# thevenin_equivalent.net
KiCad netlist of a schematic drawn in EasyEDA
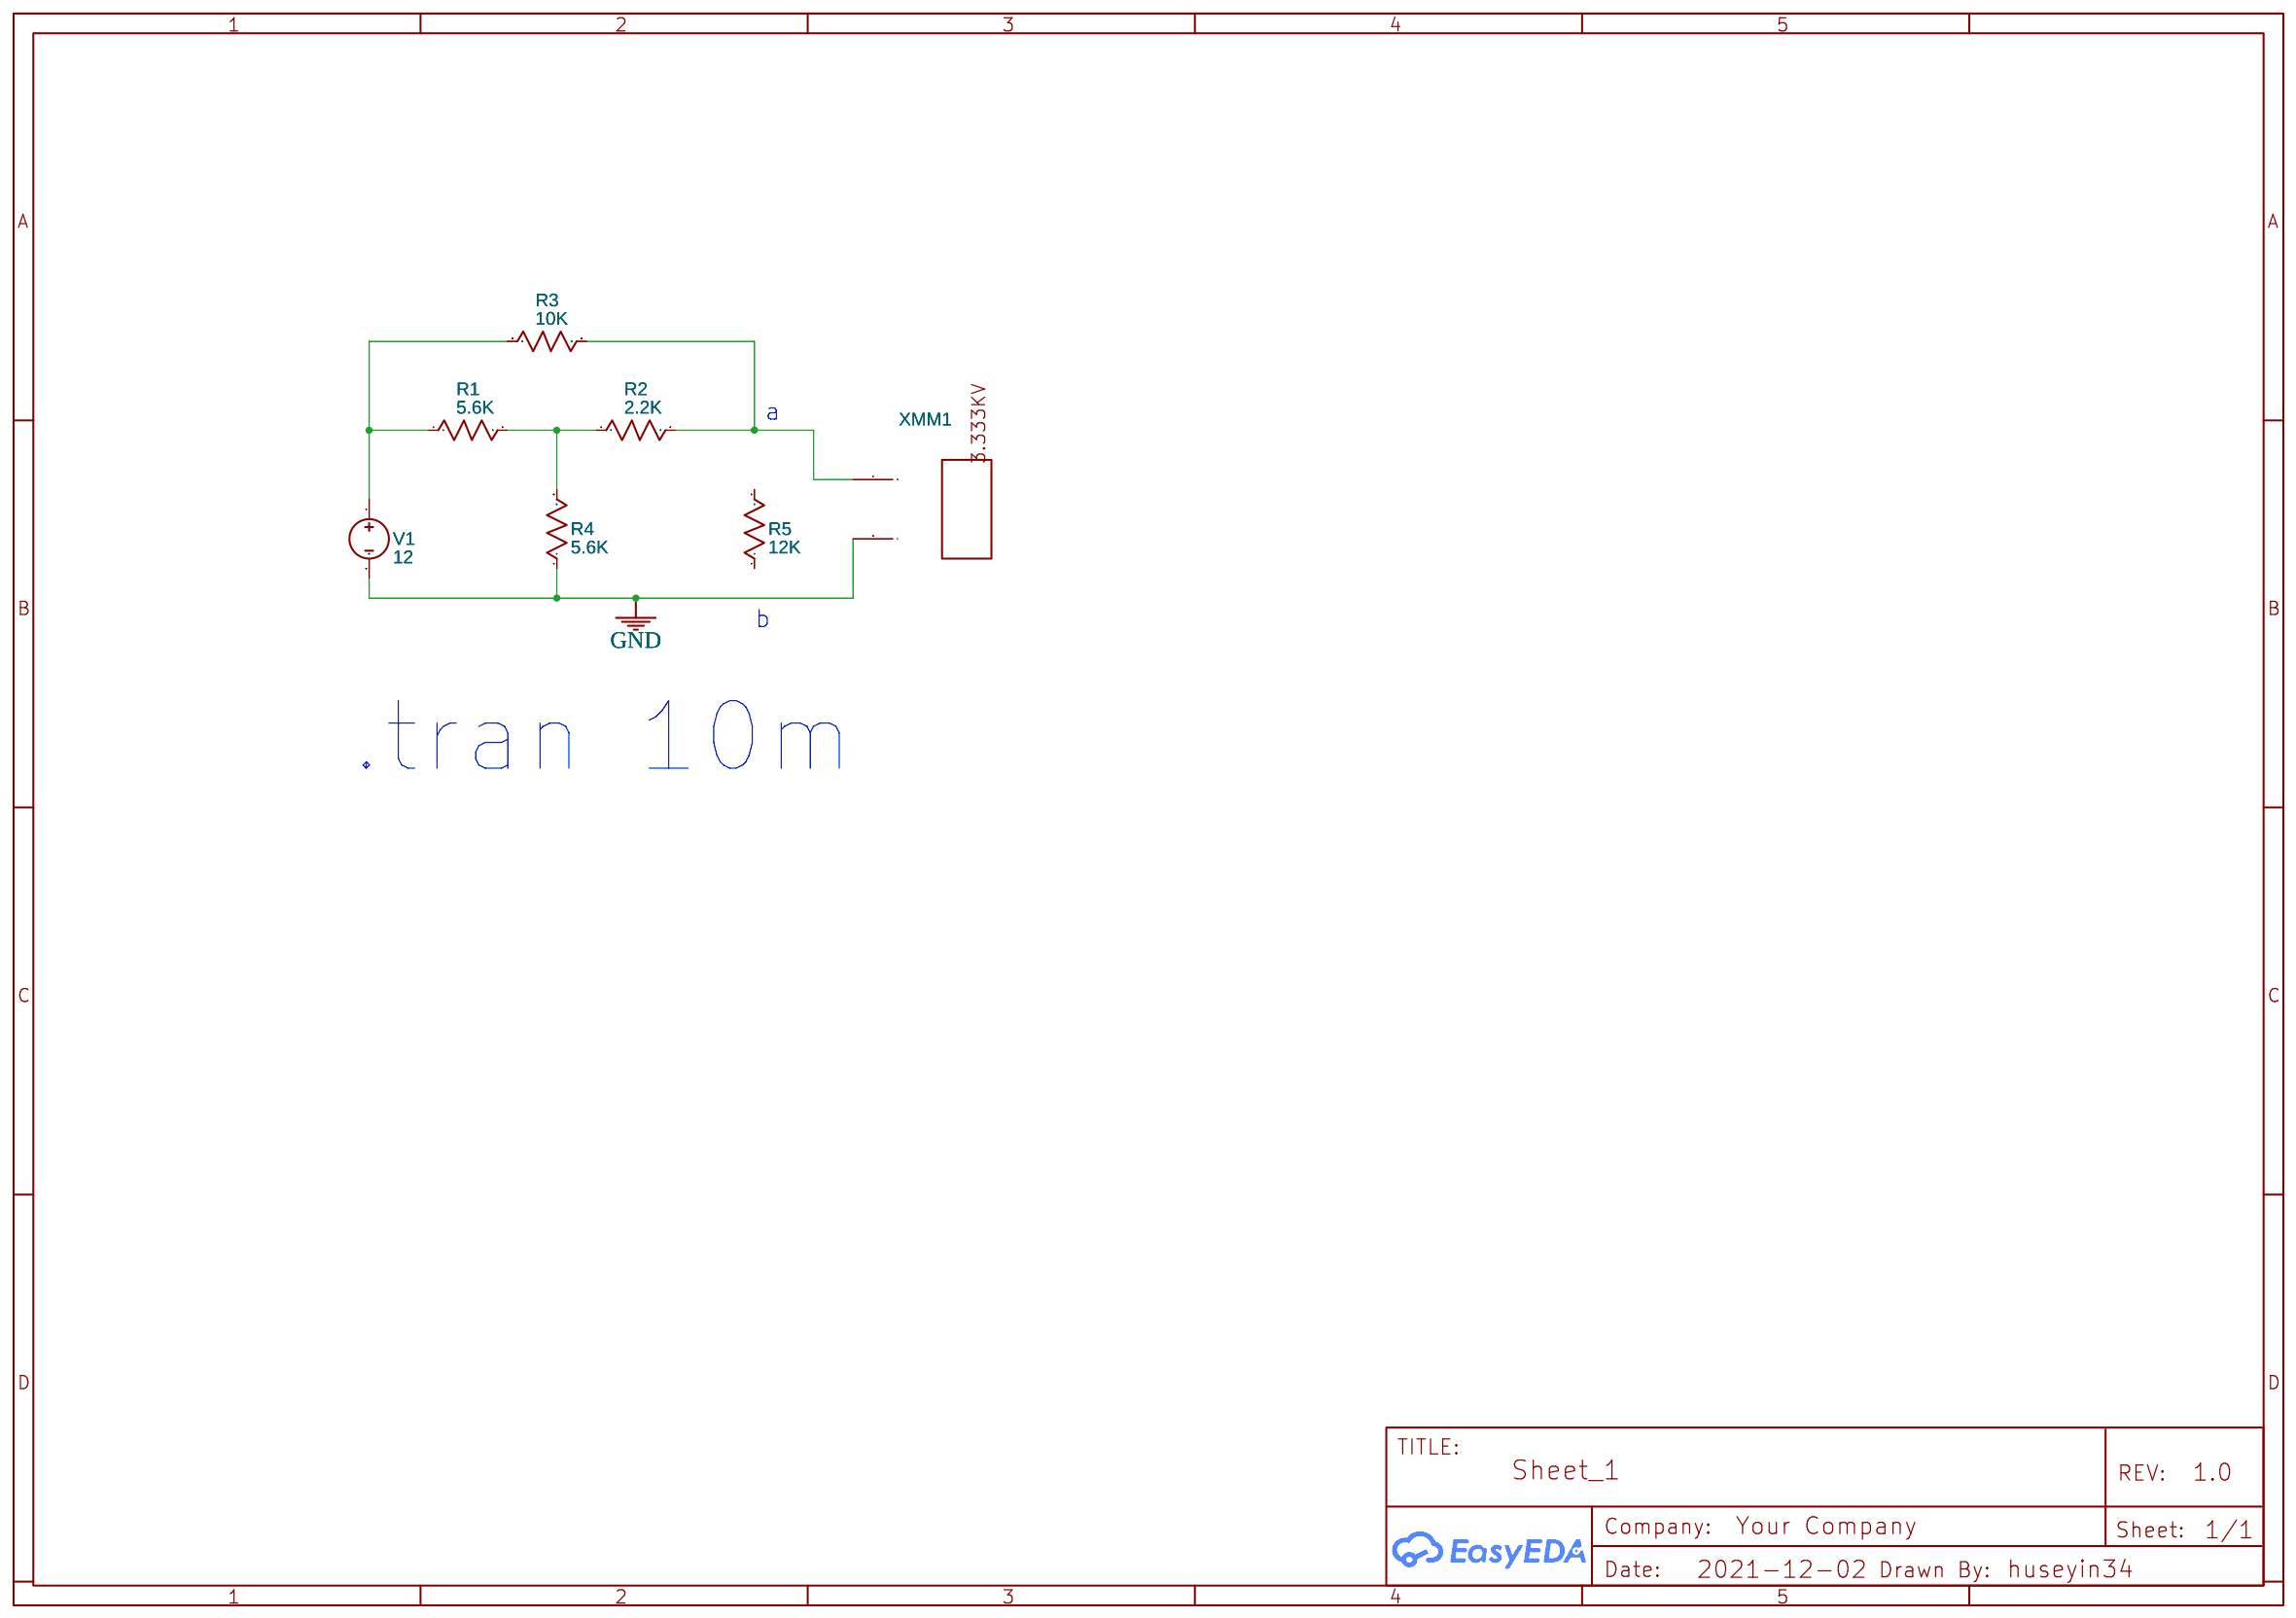
[diagram p0: fig3]
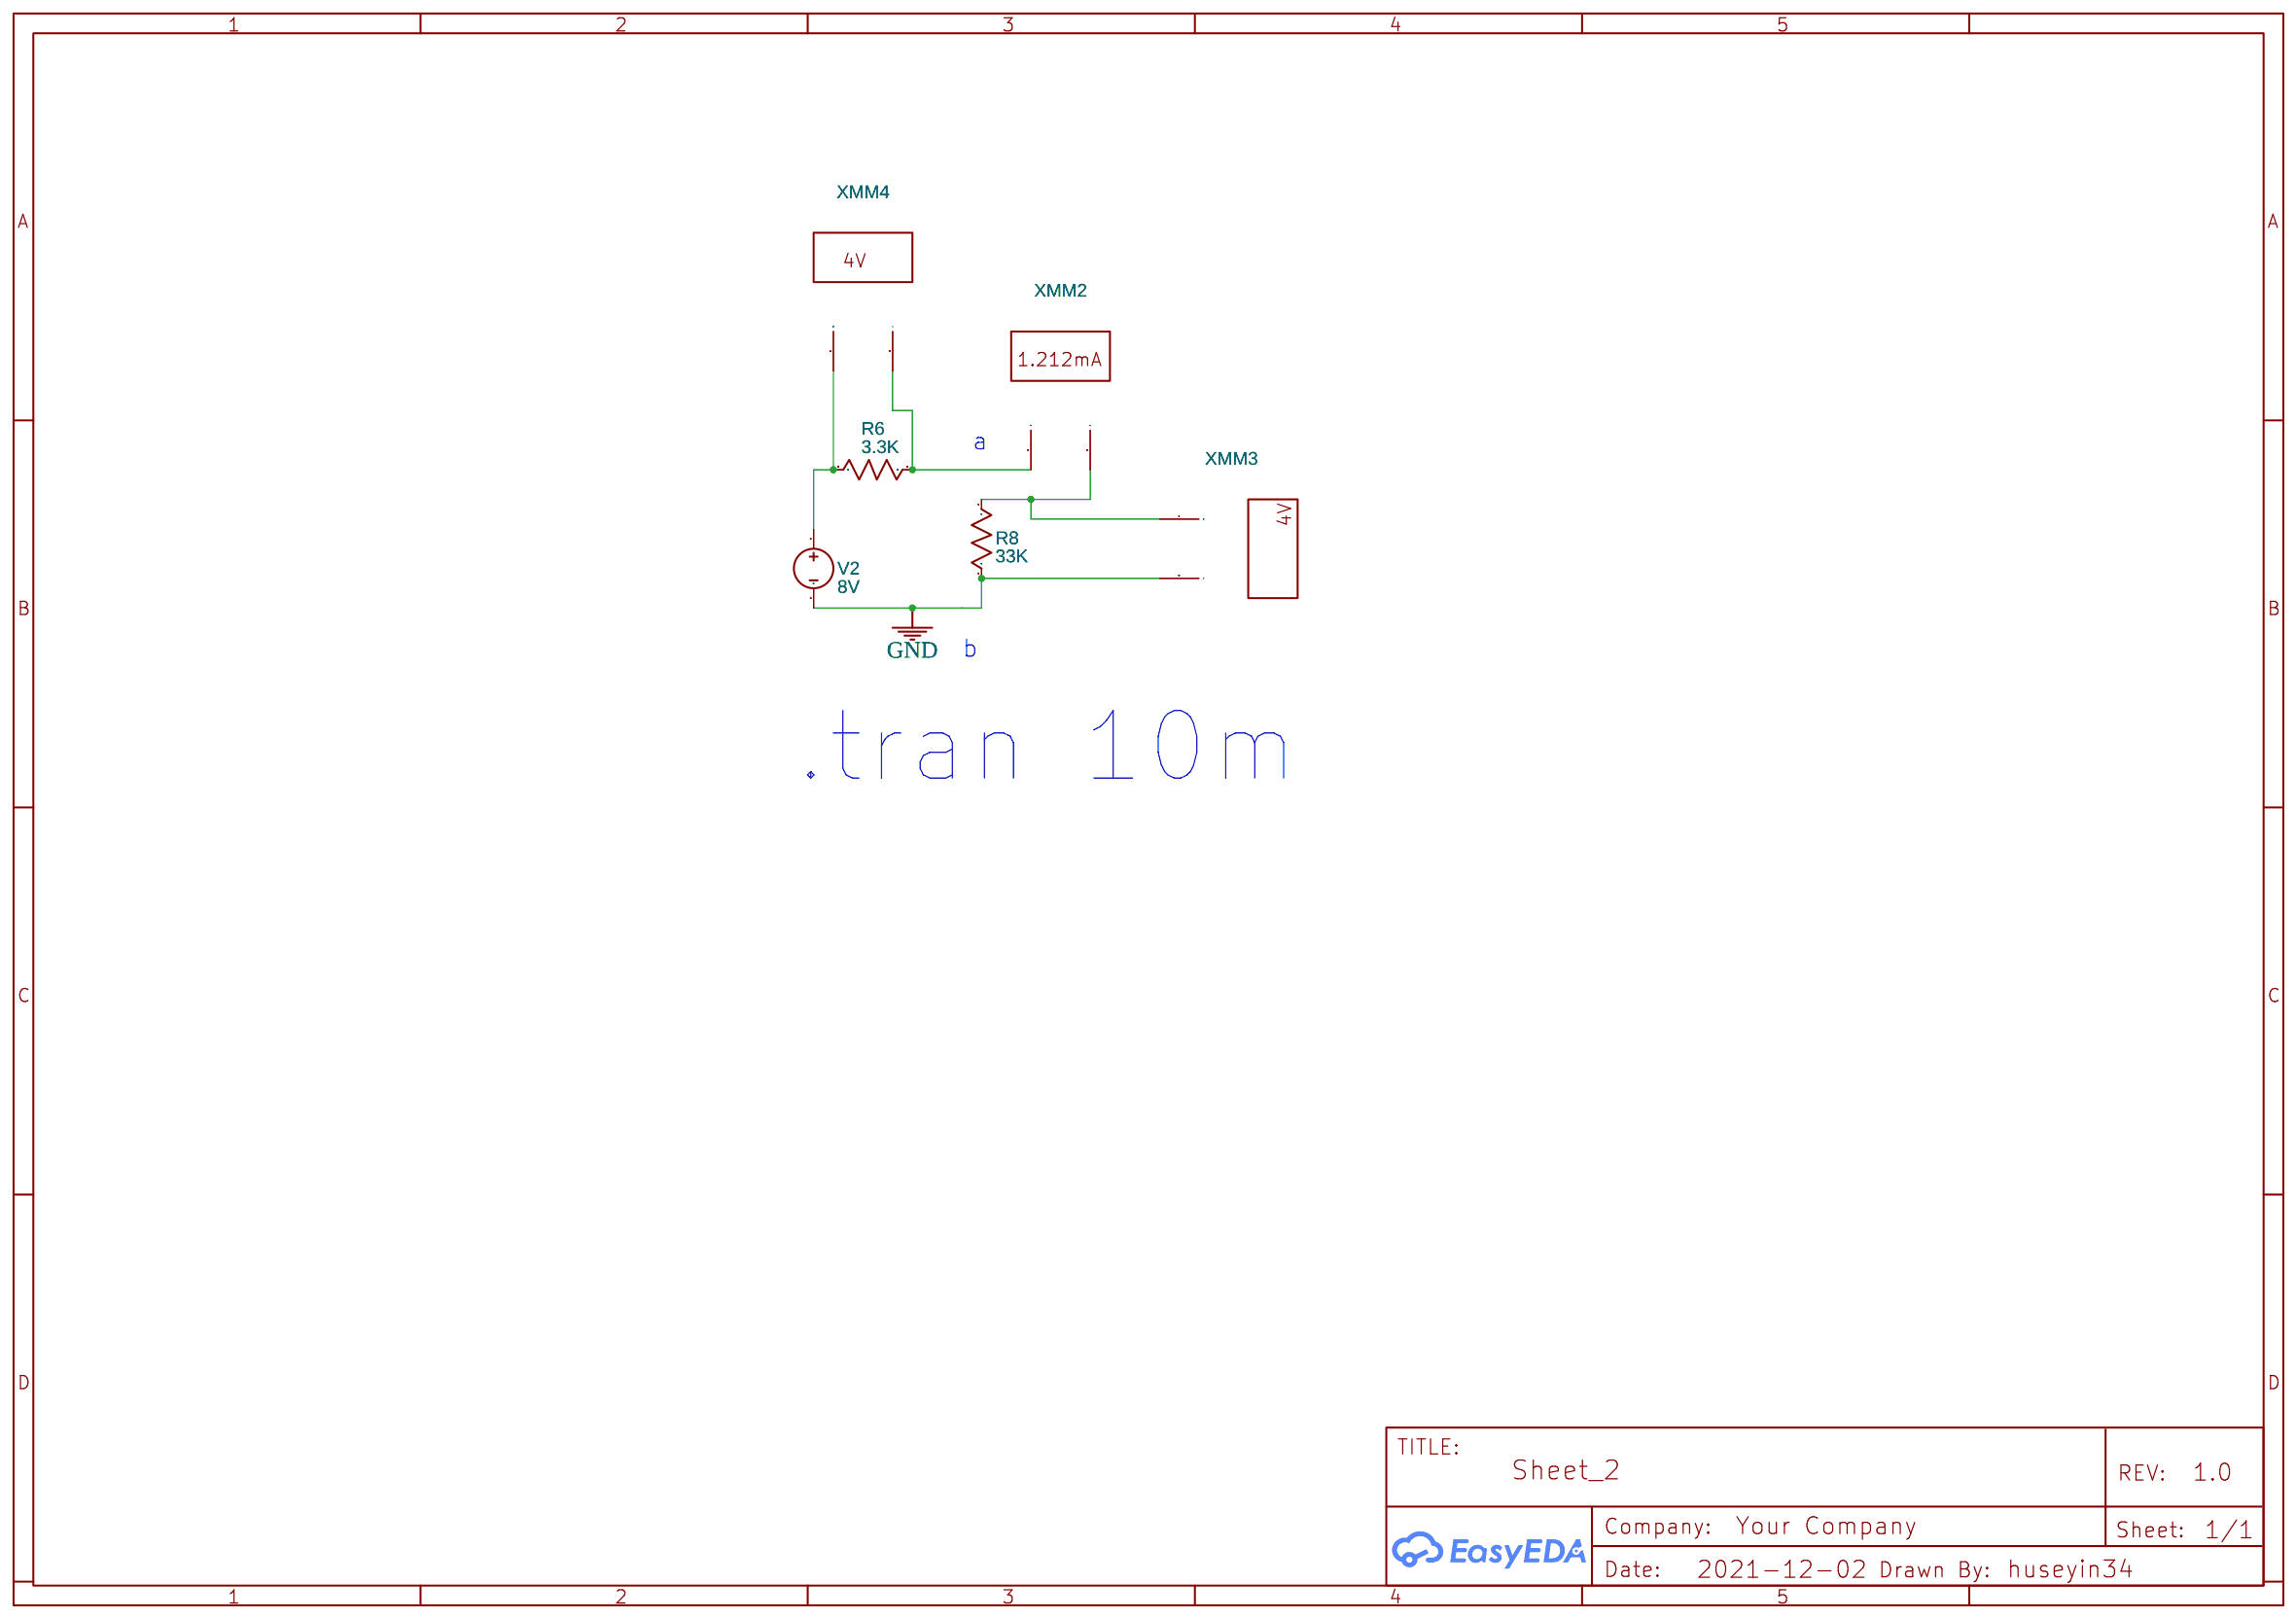
[diagram p1: thevenin equiv]
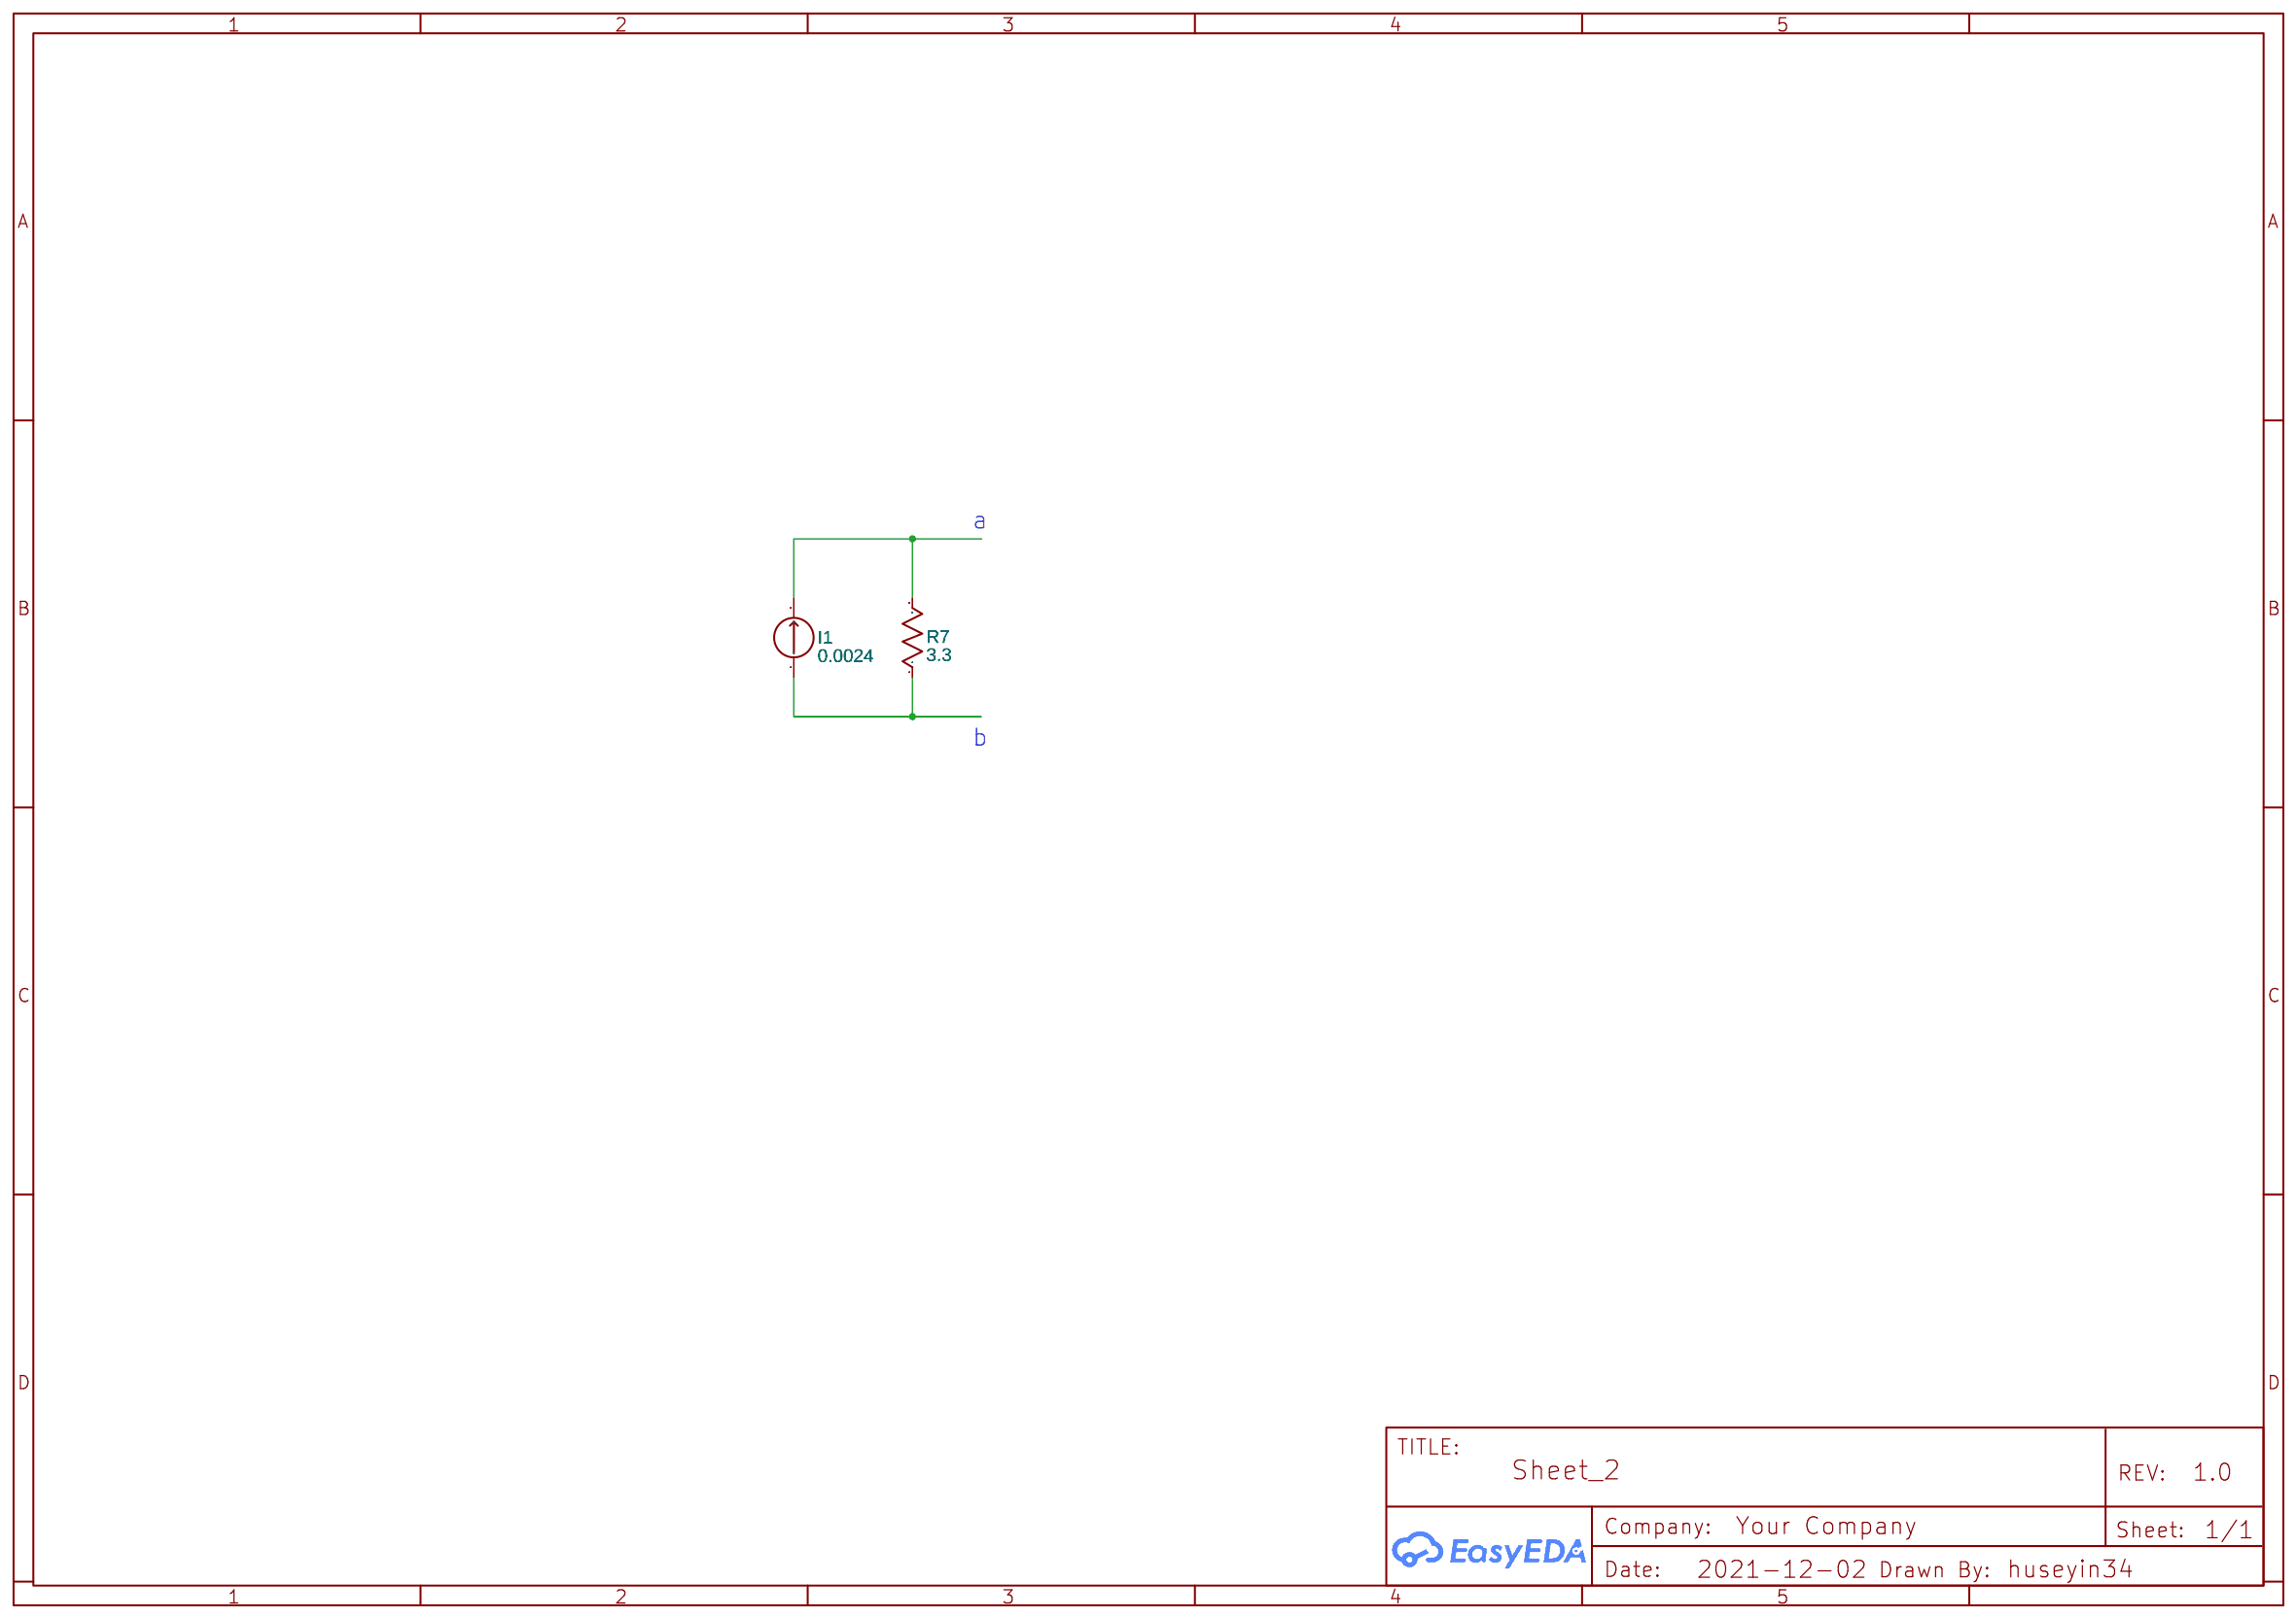
[diagram p2: Norton Equiv.]

(export (version "E")
  (design (tool "Eeschema 10.0.6"))
  (components
    (comp (ref "R1") (value "5.6K") (libsource (lib "") (part "Resistor_US_1")))
    (comp (ref "R2") (value "2.2K") (libsource (lib "") (part "Resistor_US_1")))
    (comp (ref "R3") (value "10K") (libsource (lib "") (part "Resistor_US_1")))
    (comp (ref "R4") (value "5.6K") (libsource (lib "") (part "Resistor_US")))
    (comp (ref "R5") (value "12K") (libsource (lib "") (part "Resistor_US")))
    (comp (ref "V1") (value "12") (libsource (lib "") (part "VDC")))
    (comp (ref "XMM1") (value "Multimeter") (libsource (lib "") (part "MULTIMETER")))
    (comp (ref "R6") (value "3.3K") (libsource (lib "") (part "Resistor_US")))
    (comp (ref "R8") (value "33K") (libsource (lib "") (part "Resistor_US_1")))
    (comp (ref "V2") (value "8V") (libsource (lib "") (part "VDC")))
    (comp (ref "XMM2") (value "Multimeter") (libsource (lib "") (part "MULTIMETER_2")))
    (comp (ref "XMM3") (value "Multimeter") (libsource (lib "") (part "MULTIMETER")))
    (comp (ref "XMM4") (value "Multimeter") (libsource (lib "") (part "MULTIMETER_1")))
    (comp (ref "I1") (value "0.0024") (libsource (lib "") (part "IDC")))
    (comp (ref "R7") (value "3.3") (libsource (lib "") (part "Resistor_US")))
  )
  (nets
    (net (code "1") (name "GND") (class "Default")
      (node (ref "R4") (pin "1") (pinfunction "1_1") (pintype "unspecified"))
      (node (ref "R8") (pin "1") (pinfunction "1_1") (pintype "unspecified"))
      (node (ref "V1") (pin "2") (pinfunction "2_2") (pintype "unspecified"))
      (node (ref "V2") (pin "2") (pinfunction "2_2") (pintype "unspecified"))
      (node (ref "XMM1") (pin "2") (pinfunction "I_2") (pintype "unspecified"))
      (node (ref "XMM3") (pin "2") (pinfunction "I_2") (pintype "unspecified"))
    )
    (net (code "2") (name "Net-(I1-Pad1)") (class "Default")
      (node (ref "I1") (pin "1") (pinfunction "1_1") (pintype "unspecified"))
      (node (ref "R7") (pin "1") (pinfunction "1_1") (pintype "unspecified"))
    )
    (net (code "3") (name "Net-(I1-Pad2)") (class "Default")
      (node (ref "I1") (pin "2") (pinfunction "2_2") (pintype "unspecified"))
      (node (ref "R7") (pin "2") (pinfunction "2_2") (pintype "unspecified"))
    )
    (net (code "4") (name "Net-(R1-Pad1)") (class "Default")
      (node (ref "R1") (pin "1") (pinfunction "1_1") (pintype "unspecified"))
      (node (ref "R3") (pin "1") (pinfunction "1_1") (pintype "unspecified"))
      (node (ref "V1") (pin "1") (pinfunction "1_1") (pintype "unspecified"))
    )
    (net (code "5") (name "Net-(R1-Pad2)") (class "Default")
      (node (ref "R1") (pin "2") (pinfunction "2_2") (pintype "unspecified"))
      (node (ref "R2") (pin "1") (pinfunction "1_1") (pintype "unspecified"))
      (node (ref "R4") (pin "2") (pinfunction "2_2") (pintype "unspecified"))
    )
    (net (code "6") (name "Net-(XMM1-+)") (class "Default")
      (node (ref "R2") (pin "2") (pinfunction "2_2") (pintype "unspecified"))
      (node (ref "R3") (pin "2") (pinfunction "2_2") (pintype "unspecified"))
      (node (ref "XMM1") (pin "1") (pinfunction "+_1") (pintype "unspecified"))
    )
    (net (code "7") (name "Net-(XMM2-+)") (class "Default")
      (node (ref "R6") (pin "2") (pinfunction "2_2") (pintype "unspecified"))
      (node (ref "XMM2") (pin "1") (pinfunction "+_1") (pintype "unspecified"))
      (node (ref "XMM4") (pin "2") (pinfunction "I_2") (pintype "unspecified"))
    )
    (net (code "8") (name "Net-(XMM2-I)") (class "Default")
      (node (ref "R8") (pin "2") (pinfunction "2_2") (pintype "unspecified"))
      (node (ref "XMM2") (pin "2") (pinfunction "I_2") (pintype "unspecified"))
      (node (ref "XMM3") (pin "1") (pinfunction "+_1") (pintype "unspecified"))
    )
    (net (code "9") (name "Net-(XMM4-+)") (class "Default")
      (node (ref "R6") (pin "1") (pinfunction "1_1") (pintype "unspecified"))
      (node (ref "V2") (pin "1") (pinfunction "1_1") (pintype "unspecified"))
      (node (ref "XMM4") (pin "1") (pinfunction "+_1") (pintype "unspecified"))
    )
    (net (code "10") (name "unconnected-(R5-Pad1)") (class "Default")
      (node (ref "R5") (pin "1") (pinfunction "1_1") (pintype "unspecified"))
    )
    (net (code "11") (name "unconnected-(R5-Pad2)") (class "Default")
      (node (ref "R5") (pin "2") (pinfunction "2_2") (pintype "unspecified"))
    )
  )
)
